# micro.net
KiCad netlist of a schematic drawn in Altium Designer
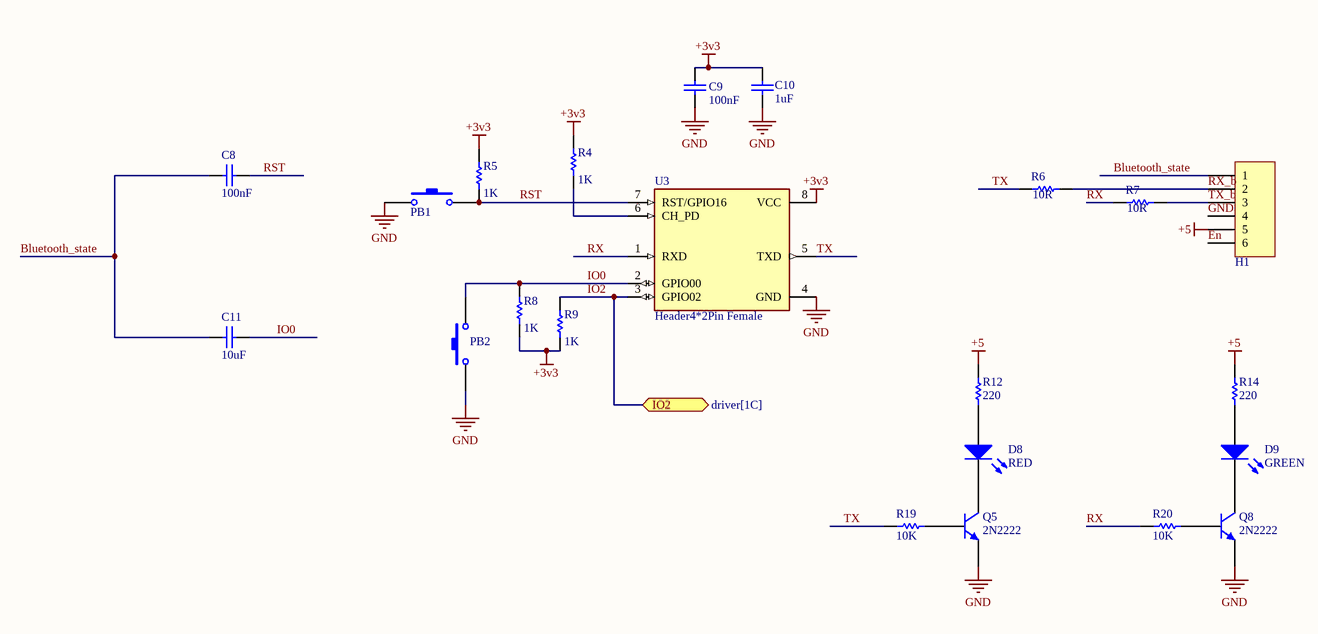
[diagram p0: micro.SchDoc]

(export (version "E")
  (design (tool "Eeschema 10.0.6"))
  (components
    (comp (ref "C8")
      (value "100nF")
      (footprint "CAP0805")
      (description "CAP seramic")
      (fields (field (name "Comment") "cap 100nF"))
      (libsource (lib "Altium library (www.AVRelec.com)") (part "Cap ceramic"))
    )
    (comp (ref "C9")
      (value "100nF")
      (footprint "CAP0805")
      (description "CAP seramic")
      (fields (field (name "Comment") "cap 100nF"))
      (libsource (lib "Altium library (www.AVRelec.com)") (part "Cap ceramic"))
    )
    (comp (ref "C10")
      (value "1uF")
      (footprint "CAP0805")
      (description "CAP seramic")
      (fields (field (name "Comment") "cap 1uF"))
      (libsource (lib "Altium library (www.AVRelec.com)") (part "Cap ceramic"))
    )
    (comp (ref "C11")
      (value "10uF")
      (footprint "CAP0805")
      (description "CAP seramic")
      (fields (field (name "Comment") "cap 10uF"))
      (libsource (lib "Altium library (www.AVRelec.com)") (part "Cap ceramic"))
    )
    (comp (ref "D8")
      (value "RED")
      (footprint "LED_0603 R")
      (description "Typical INFRARED GaAs LED")
      (fields (field (name "PUBLISHER") "Altium Limited"))
      (libsource (lib "Miscellaneous Devices") (part "LED0"))
    )
    (comp (ref "D9")
      (value "GREEN")
      (footprint "LED_0603 G")
      (description "Typical INFRARED GaAs LED")
      (fields (field (name "PUBLISHER") "Altium Limited"))
      (libsource (lib "Miscellaneous Devices") (part "LED0"))
    )
    (comp (ref "H1")
      (value "H-1x6")
      (footprint "H-1x6")
      (description "Bluetooth module HC05")
      (libsource (lib "Mine-Discreet") (part "H-1x6"))
    )
    (comp (ref "PB1")
      (value "Push-Button-tall")
      (footprint "tack-sw-3x5x6")
      (libsource (lib "Mine-Discreet") (part "Push-Button-tall"))
    )
    (comp (ref "PB2")
      (value "Push-Button-tall")
      (footprint "tack-sw-3x5x6")
      (libsource (lib "Mine-Discreet") (part "Push-Button-tall"))
    )
    (comp (ref "Q5")
      (value "2N2222")
      (footprint "SOT23_BEC_L")
      (description "NPN General Purpose Amplifier")
      (fields (field (name "PUBLISHER") "Altium Limited"))
      (libsource (lib "Miscellaneous Devices") (part "2N3904"))
    )
    (comp (ref "Q8")
      (value "2N2222")
      (footprint "SOT23_BEC_L")
      (description "NPN General Purpose Amplifier")
      (fields (field (name "PUBLISHER") "Altium Limited"))
      (libsource (lib "Miscellaneous Devices") (part "2N3904"))
    )
    (comp (ref "R4")
      (value "1K")
      (footprint "RES0805")
      (description "Resistor")
      (fields (field (name "Comment") "Res 1K") (field (name "PUBLISHER") "Altium Limited"))
      (libsource (lib "Miscellaneous Devices") (part "Res1"))
    )
    (comp (ref "R5")
      (value "1K")
      (footprint "RES0805")
      (description "Resistor")
      (fields (field (name "Comment") "Res 1K") (field (name "PUBLISHER") "Altium Limited"))
      (libsource (lib "Miscellaneous Devices") (part "Res1"))
    )
    (comp (ref "R6")
      (value "10R")
      (footprint "RES0805")
      (description "Resistor")
      (fields (field (name "Comment") "Res 10R") (field (name "PUBLISHER") "Altium Limited"))
      (libsource (lib "Miscellaneous Devices") (part "Res1"))
    )
    (comp (ref "R7")
      (value "10R")
      (footprint "RES0805")
      (description "Resistor")
      (fields (field (name "Comment") "Res 10R") (field (name "PUBLISHER") "Altium Limited"))
      (libsource (lib "Miscellaneous Devices") (part "Res1"))
    )
    (comp (ref "R8")
      (value "1K")
      (footprint "RES0805")
      (description "Resistor")
      (fields (field (name "Comment") "Res 1K") (field (name "PUBLISHER") "Altium Limited"))
      (libsource (lib "Miscellaneous Devices") (part "Res1"))
    )
    (comp (ref "R9")
      (value "1K")
      (footprint "RES0805")
      (description "Resistor")
      (fields (field (name "Comment") "Res 1K") (field (name "PUBLISHER") "Altium Limited"))
      (libsource (lib "Miscellaneous Devices") (part "Res1"))
    )
    (comp (ref "R12")
      (value "220")
      (footprint "RES0805")
      (description "Resistor")
      (fields (field (name "Comment") "Res 220") (field (name "PUBLISHER") "Altium Limited"))
      (libsource (lib "Miscellaneous Devices") (part "Res1"))
    )
    (comp (ref "R14")
      (value "220")
      (footprint "RES0805")
      (description "Resistor")
      (fields (field (name "Comment") "Res 220") (field (name "PUBLISHER") "Altium Limited"))
      (libsource (lib "Miscellaneous Devices") (part "Res1"))
    )
    (comp (ref "R19")
      (value "10K")
      (footprint "RES0805")
      (description "Resistor")
      (fields (field (name "Comment") "Res 10K") (field (name "PUBLISHER") "Altium Limited"))
      (libsource (lib "Miscellaneous Devices") (part "Res1"))
    )
    (comp (ref "R20")
      (value "10K")
      (footprint "RES0805")
      (description "Resistor")
      (fields (field (name "Comment") "Res 10K") (field (name "PUBLISHER") "Altium Limited"))
      (libsource (lib "Miscellaneous Devices") (part "Res1"))
    )
    (comp (ref "U3")
      (value "Header4*2Pin Female")
      (footprint "ESP8266-01/ESP-01")
      (description "ESP-01 wifi module")
      (fields (field (name "MP") "ESP8266-01/ESP-01") (field (name "MF") "AI-Thinker"))
      (libsource (lib "Schlib1") (part "ESP8266-01/ESP-01"))
    )
  )
  (nets
    (net (code "1") (name "+3v3") (class "Default")
      (node (ref "C10") (pin "1") (pinfunction "1_1") (pintype "passive"))
      (node (ref "C9") (pin "2") (pinfunction "2_2") (pintype "passive"))
      (node (ref "R4") (pin "1") (pinfunction "1_1") (pintype "passive"))
      (node (ref "R5") (pin "1") (pinfunction "1_1") (pintype "passive"))
      (node (ref "R8") (pin "2") (pinfunction "2_2") (pintype "passive"))
      (node (ref "R9") (pin "2") (pinfunction "2_2") (pintype "passive"))
      (node (ref "U3") (pin "8") (pinfunction "VCC_8") (pintype "power_in"))
    )
    (net (code "2") (name "+5") (class "Default")
      (node (ref "H1") (pin "5") (pinfunction "5_5") (pintype "passive"))
      (node (ref "R12") (pin "2") (pinfunction "2_2") (pintype "passive"))
      (node (ref "R14") (pin "2") (pinfunction "2_2") (pintype "passive"))
    )
    (net (code "3") (name "/Bluetooth_state") (class "Default")
      (node (ref "C11") (pin "2") (pinfunction "2_2") (pintype "passive"))
      (node (ref "C8") (pin "2") (pinfunction "2_2") (pintype "passive"))
      (node (ref "H1") (pin "1") (pinfunction "1_1") (pintype "passive"))
    )
    (net (code "4") (name "/En") (class "Default")
      (node (ref "H1") (pin "6") (pinfunction "6_6") (pintype "passive"))
    )
    (net (code "5") (name "/IO0") (class "Default")
      (node (ref "C11") (pin "1") (pinfunction "1_1") (pintype "passive"))
      (node (ref "PB2") (pin "2") (pinfunction "2_2") (pintype "passive"))
      (node (ref "R8") (pin "1") (pinfunction "1_1") (pintype "passive"))
      (node (ref "U3") (pin "2") (pinfunction "GPIO00_2") (pintype "bidirectional"))
    )
    (net (code "6") (name "/IO2") (class "Default")
      (node (ref "R9") (pin "1") (pinfunction "1_1") (pintype "passive"))
      (node (ref "U3") (pin "3") (pinfunction "GPIO02_3") (pintype "bidirectional"))
    )
    (net (code "7") (name "/RST") (class "Default")
      (node (ref "C8") (pin "1") (pinfunction "1_1") (pintype "passive"))
      (node (ref "PB1") (pin "2") (pinfunction "2_2") (pintype "passive"))
      (node (ref "R5") (pin "2") (pinfunction "2_2") (pintype "passive"))
      (node (ref "U3") (pin "7") (pinfunction "RST/GPIO16_7") (pintype "input"))
    )
    (net (code "8") (name "/RX") (class "Default")
      (node (ref "R20") (pin "1") (pinfunction "1_1") (pintype "passive"))
      (node (ref "R7") (pin "2") (pinfunction "2_2") (pintype "passive"))
      (node (ref "U3") (pin "1") (pinfunction "RXD_1") (pintype "input"))
    )
    (net (code "9") (name "/RX_b") (class "Default")
      (node (ref "H1") (pin "2") (pinfunction "2_2") (pintype "passive"))
      (node (ref "R6") (pin "2") (pinfunction "2_2") (pintype "passive"))
    )
    (net (code "10") (name "/TX") (class "Default")
      (node (ref "R19") (pin "1") (pinfunction "1_1") (pintype "passive"))
      (node (ref "R6") (pin "1") (pinfunction "1_1") (pintype "passive"))
      (node (ref "U3") (pin "5") (pinfunction "TXD_5") (pintype "output"))
    )
    (net (code "11") (name "/TX_b") (class "Default")
      (node (ref "H1") (pin "3") (pinfunction "3_3") (pintype "passive"))
      (node (ref "R7") (pin "1") (pinfunction "1_1") (pintype "passive"))
    )
    (net (code "12") (name "GND") (class "Default")
      (node (ref "C10") (pin "2") (pinfunction "2_2") (pintype "passive"))
      (node (ref "C9") (pin "1") (pinfunction "1_1") (pintype "passive"))
      (node (ref "H1") (pin "4") (pinfunction "4_4") (pintype "passive"))
      (node (ref "PB1") (pin "1") (pinfunction "1_1") (pintype "passive"))
      (node (ref "PB2") (pin "1") (pinfunction "1_1") (pintype "passive"))
      (node (ref "Q5") (pin "1") (pinfunction "E_1") (pintype "passive"))
      (node (ref "Q8") (pin "1") (pinfunction "E_1") (pintype "passive"))
      (node (ref "U3") (pin "4") (pinfunction "GND_4") (pintype "power_in"))
    )
    (net (code "13") (name "Net-(D8-A)") (class "Default")
      (node (ref "D8") (pin "1") (pinfunction "A_1") (pintype "passive"))
      (node (ref "R12") (pin "1") (pinfunction "1_1") (pintype "passive"))
    )
    (net (code "14") (name "Net-(D8-K)") (class "Default")
      (node (ref "D8") (pin "2") (pinfunction "K_2") (pintype "passive"))
      (node (ref "Q5") (pin "3") (pinfunction "C_3") (pintype "passive"))
    )
    (net (code "15") (name "Net-(D9-A)") (class "Default")
      (node (ref "D9") (pin "1") (pinfunction "A_1") (pintype "passive"))
      (node (ref "R14") (pin "1") (pinfunction "1_1") (pintype "passive"))
    )
    (net (code "16") (name "Net-(D9-K)") (class "Default")
      (node (ref "D9") (pin "2") (pinfunction "K_2") (pintype "passive"))
      (node (ref "Q8") (pin "3") (pinfunction "C_3") (pintype "passive"))
    )
    (net (code "17") (name "Net-(Q5-B)") (class "Default")
      (node (ref "Q5") (pin "2") (pinfunction "B_2") (pintype "passive"))
      (node (ref "R19") (pin "2") (pinfunction "2_2") (pintype "passive"))
    )
    (net (code "18") (name "Net-(Q8-B)") (class "Default")
      (node (ref "Q8") (pin "2") (pinfunction "B_2") (pintype "passive"))
      (node (ref "R20") (pin "2") (pinfunction "2_2") (pintype "passive"))
    )
    (net (code "19") (name "Net-(U3-CH_PD)") (class "Default")
      (node (ref "R4") (pin "2") (pinfunction "2_2") (pintype "passive"))
      (node (ref "U3") (pin "6") (pinfunction "CH_PD_6") (pintype "input"))
    )
  )
)
